# 03200904.net
KiCad netlist of a schematic drawn in Altium Designer
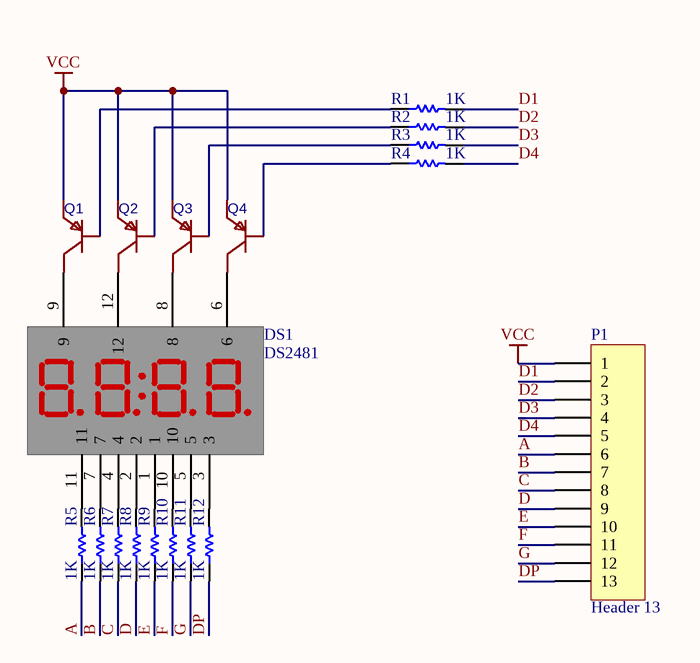
[diagram p0: 03200904张晨.SchDoc]

(export (version "E")
  (design (tool "Eeschema 10.0.6"))
  (components
    (comp (ref "DS1") (value "DS2481") (footprint "DS2481") (libsource (lib "LEDKEY") (part "DS2481")))
    (comp (ref "P1")
      (value "Header 13")
      (footprint "HDR1X13")
      (description "Header, 13-Pin")
      (fields (field (name "PUBLISHER") "Altium Limited"))
      (libsource (lib "Miscellaneous Connectors") (part "Header 13"))
    )
    (comp (ref "Q1")
      (value "SS8550_C541706")
      (footprint "SOT-23-3")
      (fields
        (field (name "BOM_SUPPLIER PART") "C541706")
        (field (name "BOM_MANUFACTURER PART") "SS8550")
        (field (name "CONTRIBUTOR") "LCSC")
      )
      (libsource (lib "LEDKEY") (part "SS8550_C541706"))
    )
    (comp (ref "Q2")
      (value "SS8550_C541706")
      (footprint "SOT-23-3")
      (fields
        (field (name "BOM_SUPPLIER PART") "C541706")
        (field (name "BOM_MANUFACTURER PART") "SS8550")
        (field (name "CONTRIBUTOR") "LCSC")
      )
      (libsource (lib "LEDKEY") (part "SS8550_C541706"))
    )
    (comp (ref "Q3")
      (value "SS8550_C541706")
      (footprint "SOT-23-3")
      (fields
        (field (name "BOM_SUPPLIER PART") "C541706")
        (field (name "BOM_MANUFACTURER PART") "SS8550")
        (field (name "CONTRIBUTOR") "LCSC")
      )
      (libsource (lib "LEDKEY") (part "SS8550_C541706"))
    )
    (comp (ref "Q4")
      (value "SS8550_C541706")
      (footprint "SOT-23-3")
      (fields
        (field (name "BOM_SUPPLIER PART") "C541706")
        (field (name "BOM_MANUFACTURER PART") "SS8550")
        (field (name "CONTRIBUTOR") "LCSC")
      )
      (libsource (lib "LEDKEY") (part "SS8550_C541706"))
    )
    (comp (ref "R1")
      (value "1K")
      (footprint "R0603")
      (description "Resistor")
      (fields (field (name "Comment") "Res1") (field (name "PUBLISHER") "Altium Limited"))
      (libsource (lib "LEDKEY") (part "Res"))
    )
    (comp (ref "R2")
      (value "1K")
      (footprint "R0603")
      (description "Resistor")
      (fields (field (name "Comment") "Res1") (field (name "PUBLISHER") "Altium Limited"))
      (libsource (lib "LEDKEY") (part "Res"))
    )
    (comp (ref "R3")
      (value "1K")
      (footprint "R0603")
      (description "Resistor")
      (fields (field (name "Comment") "Res1") (field (name "PUBLISHER") "Altium Limited"))
      (libsource (lib "LEDKEY") (part "Res"))
    )
    (comp (ref "R4")
      (value "1K")
      (footprint "R0603")
      (description "Resistor")
      (fields (field (name "Comment") "Res1") (field (name "PUBLISHER") "Altium Limited"))
      (libsource (lib "LEDKEY") (part "Res"))
    )
    (comp (ref "R5")
      (value "1K")
      (footprint "R0603")
      (description "Resistor")
      (fields (field (name "Comment") "Res1") (field (name "PUBLISHER") "Altium Limited"))
      (libsource (lib "LEDKEY") (part "Res"))
    )
    (comp (ref "R6")
      (value "1K")
      (footprint "R0603")
      (description "Resistor")
      (fields (field (name "Comment") "Res1") (field (name "PUBLISHER") "Altium Limited"))
      (libsource (lib "LEDKEY") (part "Res"))
    )
    (comp (ref "R7")
      (value "1K")
      (footprint "R0603")
      (description "Resistor")
      (fields (field (name "Comment") "Res1") (field (name "PUBLISHER") "Altium Limited"))
      (libsource (lib "LEDKEY") (part "Res"))
    )
    (comp (ref "R8")
      (value "1K")
      (footprint "R0603")
      (description "Resistor")
      (fields (field (name "Comment") "Res1") (field (name "PUBLISHER") "Altium Limited"))
      (libsource (lib "LEDKEY") (part "Res"))
    )
    (comp (ref "R9")
      (value "1K")
      (footprint "R0603")
      (description "Resistor")
      (fields (field (name "Comment") "Res1") (field (name "PUBLISHER") "Altium Limited"))
      (libsource (lib "LEDKEY") (part "Res"))
    )
    (comp (ref "R10")
      (value "1K")
      (footprint "R0603")
      (description "Resistor")
      (fields (field (name "Comment") "Res1") (field (name "PUBLISHER") "Altium Limited"))
      (libsource (lib "LEDKEY") (part "Res"))
    )
    (comp (ref "R11")
      (value "1K")
      (footprint "R0603")
      (description "Resistor")
      (fields (field (name "Comment") "Res1") (field (name "PUBLISHER") "Altium Limited"))
      (libsource (lib "LEDKEY") (part "Res"))
    )
    (comp (ref "R12")
      (value "1K")
      (footprint "R0603")
      (description "Resistor")
      (fields (field (name "Comment") "Res1") (field (name "PUBLISHER") "Altium Limited"))
      (libsource (lib "LEDKEY") (part "Res"))
    )
  )
  (nets
    (net (code "1") (name "/A") (class "Default")
      (node (ref "P1") (pin "6") (pinfunction "6_6") (pintype "passive"))
      (node (ref "R5") (pin "1") (pinfunction "1_1") (pintype "passive"))
    )
    (net (code "2") (name "/B") (class "Default")
      (node (ref "P1") (pin "7") (pinfunction "7_7") (pintype "passive"))
      (node (ref "R6") (pin "1") (pinfunction "1_1") (pintype "passive"))
    )
    (net (code "3") (name "/C") (class "Default")
      (node (ref "P1") (pin "8") (pinfunction "8_8") (pintype "passive"))
      (node (ref "R7") (pin "1") (pinfunction "1_1") (pintype "passive"))
    )
    (net (code "4") (name "/D") (class "Default")
      (node (ref "P1") (pin "9") (pinfunction "9_9") (pintype "passive"))
      (node (ref "R8") (pin "1") (pinfunction "1_1") (pintype "passive"))
    )
    (net (code "5") (name "/D1") (class "Default")
      (node (ref "P1") (pin "2") (pinfunction "2_2") (pintype "passive"))
      (node (ref "R1") (pin "2") (pinfunction "2_2") (pintype "passive"))
    )
    (net (code "6") (name "/D2") (class "Default")
      (node (ref "P1") (pin "3") (pinfunction "3_3") (pintype "passive"))
      (node (ref "R2") (pin "2") (pinfunction "2_2") (pintype "passive"))
    )
    (net (code "7") (name "/D3") (class "Default")
      (node (ref "P1") (pin "4") (pinfunction "4_4") (pintype "passive"))
      (node (ref "R3") (pin "2") (pinfunction "2_2") (pintype "passive"))
    )
    (net (code "8") (name "/D4") (class "Default")
      (node (ref "P1") (pin "5") (pinfunction "5_5") (pintype "passive"))
      (node (ref "R4") (pin "2") (pinfunction "2_2") (pintype "passive"))
    )
    (net (code "9") (name "/DP") (class "Default")
      (node (ref "P1") (pin "13") (pinfunction "13_13") (pintype "passive"))
      (node (ref "R12") (pin "1") (pinfunction "1_1") (pintype "passive"))
    )
    (net (code "10") (name "/E") (class "Default")
      (node (ref "P1") (pin "10") (pinfunction "10_10") (pintype "passive"))
      (node (ref "R9") (pin "1") (pinfunction "1_1") (pintype "passive"))
    )
    (net (code "11") (name "/F") (class "Default")
      (node (ref "P1") (pin "11") (pinfunction "11_11") (pintype "passive"))
      (node (ref "R10") (pin "1") (pinfunction "1_1") (pintype "passive"))
    )
    (net (code "12") (name "/G") (class "Default")
      (node (ref "P1") (pin "12") (pinfunction "12_12") (pintype "passive"))
      (node (ref "R11") (pin "1") (pinfunction "1_1") (pintype "passive"))
    )
    (net (code "13") (name "Net-(DS1-Pad1)") (class "Default")
      (node (ref "DS1") (pin "1") (pinfunction "1_1") (pintype "passive"))
      (node (ref "R9") (pin "2") (pinfunction "2_2") (pintype "passive"))
    )
    (net (code "14") (name "Net-(DS1-Pad2)") (class "Default")
      (node (ref "DS1") (pin "2") (pinfunction "2_2") (pintype "passive"))
      (node (ref "R8") (pin "2") (pinfunction "2_2") (pintype "passive"))
    )
    (net (code "15") (name "Net-(DS1-Pad3)") (class "Default")
      (node (ref "DS1") (pin "3") (pinfunction "3_3") (pintype "passive"))
      (node (ref "R12") (pin "2") (pinfunction "2_2") (pintype "passive"))
    )
    (net (code "16") (name "Net-(DS1-Pad4)") (class "Default")
      (node (ref "DS1") (pin "4") (pinfunction "4_4") (pintype "passive"))
      (node (ref "R7") (pin "2") (pinfunction "2_2") (pintype "passive"))
    )
    (net (code "17") (name "Net-(DS1-Pad5)") (class "Default")
      (node (ref "DS1") (pin "5") (pinfunction "5_5") (pintype "passive"))
      (node (ref "R11") (pin "2") (pinfunction "2_2") (pintype "passive"))
    )
    (net (code "18") (name "Net-(DS1-Pad7)") (class "Default")
      (node (ref "DS1") (pin "7") (pinfunction "7_7") (pintype "passive"))
      (node (ref "R6") (pin "2") (pinfunction "2_2") (pintype "passive"))
    )
    (net (code "19") (name "Net-(DS1-Pad10)") (class "Default")
      (node (ref "DS1") (pin "10") (pinfunction "10_10") (pintype "passive"))
      (node (ref "R10") (pin "2") (pinfunction "2_2") (pintype "passive"))
    )
    (net (code "20") (name "Net-(DS1-Pad11)") (class "Default")
      (node (ref "DS1") (pin "11") (pinfunction "11_11") (pintype "passive"))
      (node (ref "R5") (pin "2") (pinfunction "2_2") (pintype "passive"))
    )
    (net (code "21") (name "Net-(Q1-B)") (class "Default")
      (node (ref "Q1") (pin "1") (pinfunction "B_1") (pintype "passive"))
      (node (ref "R1") (pin "1") (pinfunction "1_1") (pintype "passive"))
    )
    (net (code "22") (name "Net-(Q1-C)") (class "Default")
      (node (ref "DS1") (pin "9") (pinfunction "9_9") (pintype "passive"))
      (node (ref "Q1") (pin "3") (pinfunction "C_3") (pintype "passive"))
    )
    (net (code "23") (name "Net-(Q2-B)") (class "Default")
      (node (ref "Q2") (pin "1") (pinfunction "B_1") (pintype "passive"))
      (node (ref "R2") (pin "1") (pinfunction "1_1") (pintype "passive"))
    )
    (net (code "24") (name "Net-(Q2-C)") (class "Default")
      (node (ref "DS1") (pin "12") (pinfunction "12_12") (pintype "passive"))
      (node (ref "Q2") (pin "3") (pinfunction "C_3") (pintype "passive"))
    )
    (net (code "25") (name "Net-(Q3-B)") (class "Default")
      (node (ref "Q3") (pin "1") (pinfunction "B_1") (pintype "passive"))
      (node (ref "R3") (pin "1") (pinfunction "1_1") (pintype "passive"))
    )
    (net (code "26") (name "Net-(Q3-C)") (class "Default")
      (node (ref "DS1") (pin "8") (pinfunction "8_8") (pintype "passive"))
      (node (ref "Q3") (pin "3") (pinfunction "C_3") (pintype "passive"))
    )
    (net (code "27") (name "Net-(Q4-B)") (class "Default")
      (node (ref "Q4") (pin "1") (pinfunction "B_1") (pintype "passive"))
      (node (ref "R4") (pin "1") (pinfunction "1_1") (pintype "passive"))
    )
    (net (code "28") (name "Net-(Q4-C)") (class "Default")
      (node (ref "DS1") (pin "6") (pinfunction "6_6") (pintype "passive"))
      (node (ref "Q4") (pin "3") (pinfunction "C_3") (pintype "passive"))
    )
    (net (code "29") (name "VCC") (class "Default")
      (node (ref "P1") (pin "1") (pinfunction "1_1") (pintype "passive"))
      (node (ref "Q1") (pin "2") (pinfunction "E_2") (pintype "passive"))
      (node (ref "Q2") (pin "2") (pinfunction "E_2") (pintype "passive"))
      (node (ref "Q3") (pin "2") (pinfunction "E_2") (pintype "passive"))
      (node (ref "Q4") (pin "2") (pinfunction "E_2") (pintype "passive"))
    )
  )
)
